# ESP32Shield.net
KiCad netlist of a schematic drawn in EAGLE
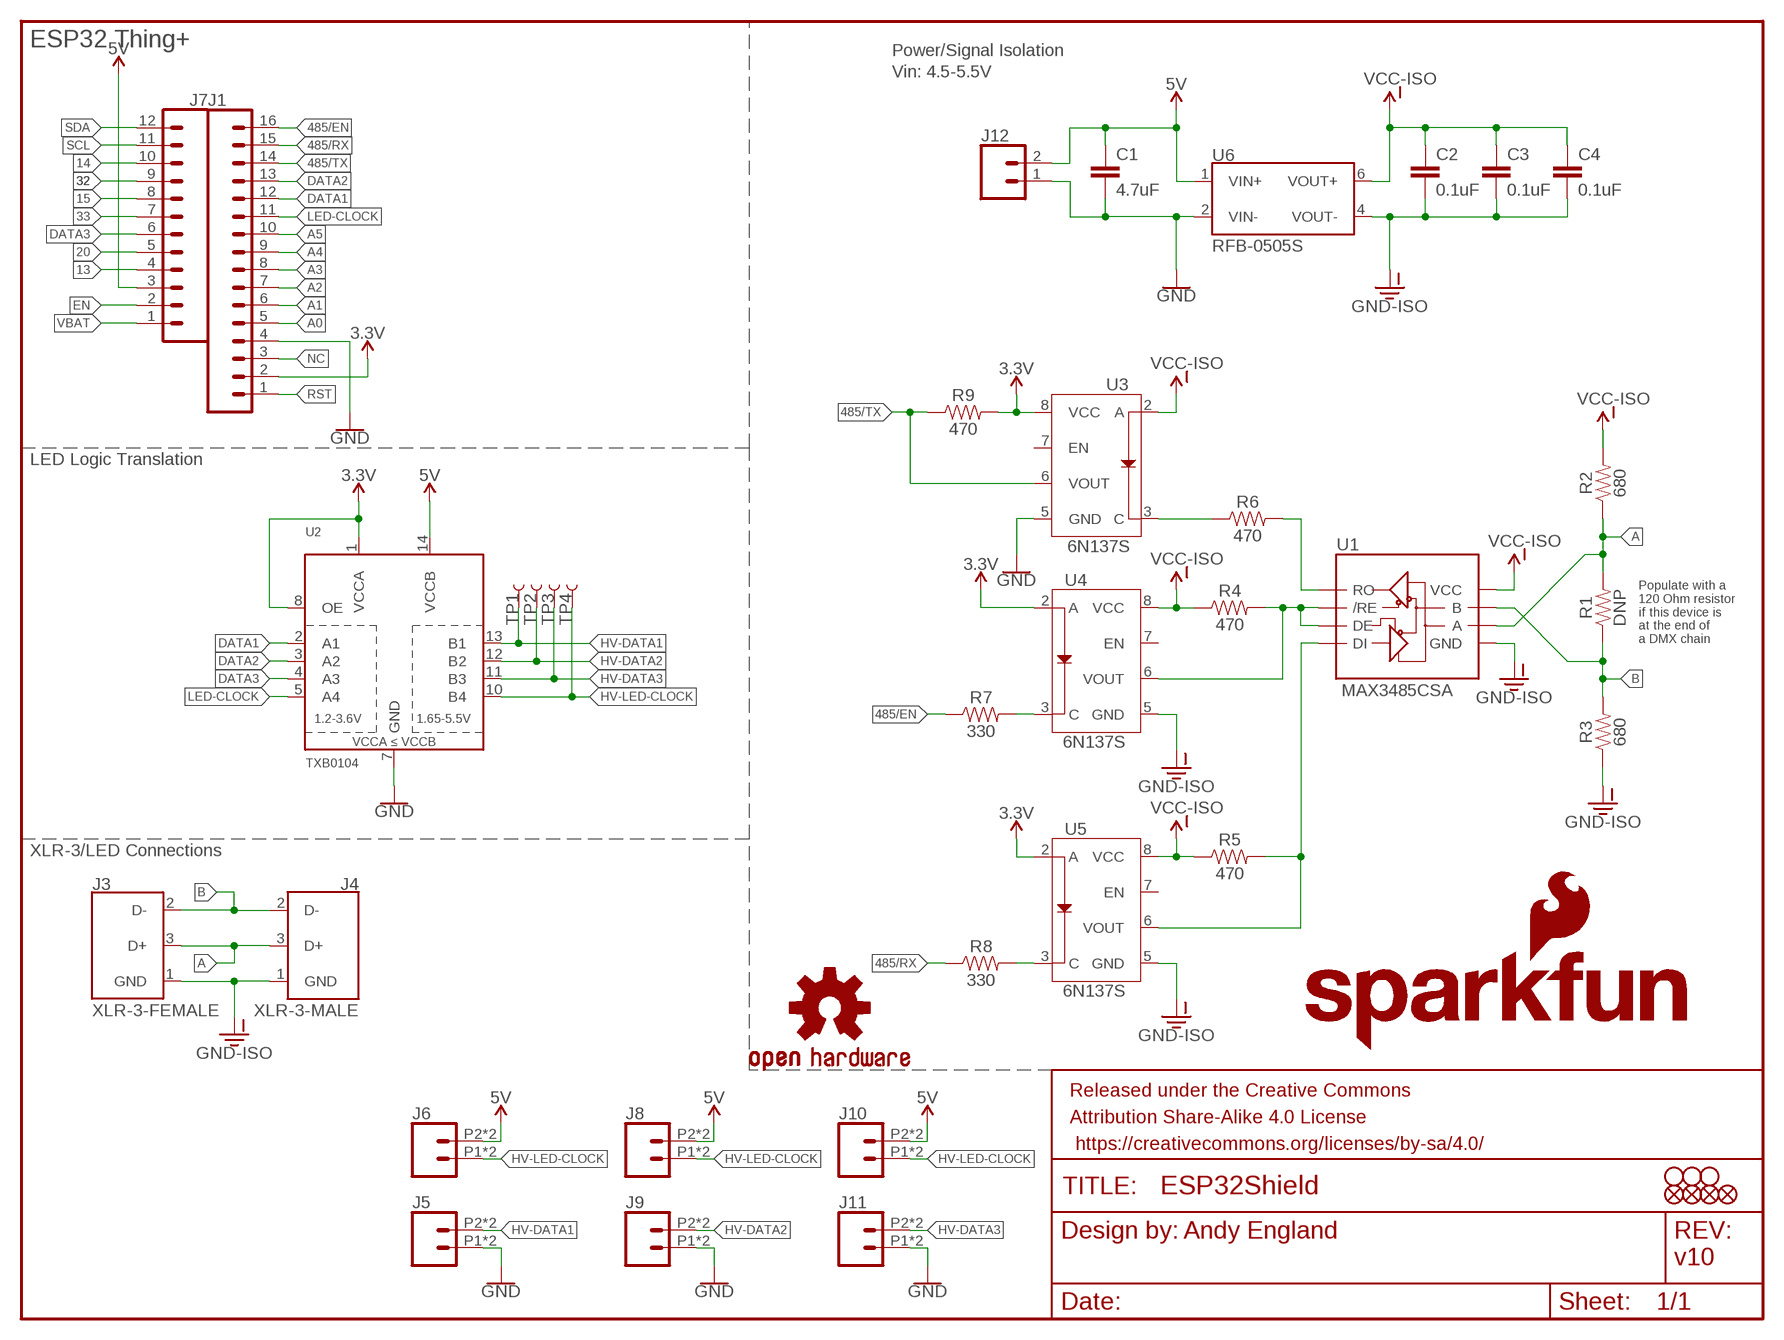
[diagram p0: schematic, sheet 1]

(export (version "E")
  (design (tool "Eeschema 10.0.6"))
  (components
    (comp (ref "C1")
      (value "4.7uF")
      (footprint "eagle-import:0603")
      (libsource (lib "eagle-import") (part "4.7UF-0603-6.3V-(10%)"))
    )
    (comp (ref "C2")
      (value "0.1uF")
      (footprint "eagle-import:0603")
      (libsource (lib "eagle-import") (part "0.1UF-0603-25V-(+80/-20%)"))
    )
    (comp (ref "C3")
      (value "0.1uF")
      (footprint "eagle-import:0603")
      (libsource (lib "eagle-import") (part "0.1UF-0603-25V-(+80/-20%)"))
    )
    (comp (ref "C4")
      (value "0.1uF")
      (footprint "eagle-import:0603")
      (libsource (lib "eagle-import") (part "0.1UF-0603-25V-(+80/-20%)"))
    )
    (comp (ref "FD1")
      (value "FIDUCIALUFIDUCIAL")
      (footprint "eagle-import:FIDUCIAL-MICRO")
      (libsource (lib "eagle-import") (part "FIDUCIALUFIDUCIAL"))
    )
    (comp (ref "FD2")
      (value "FIDUCIALUFIDUCIAL")
      (footprint "eagle-import:FIDUCIAL-MICRO")
      (libsource (lib "eagle-import") (part "FIDUCIALUFIDUCIAL"))
    )
    (comp (ref "FD3")
      (value "FIDUCIALUFIDUCIAL")
      (footprint "eagle-import:FIDUCIAL-MICRO")
      (libsource (lib "eagle-import") (part "FIDUCIALUFIDUCIAL"))
    )
    (comp (ref "FD4")
      (value "FIDUCIALUFIDUCIAL")
      (footprint "eagle-import:FIDUCIAL-MICRO")
      (libsource (lib "eagle-import") (part "FIDUCIALUFIDUCIAL"))
    )
    (comp (ref "FRAME1")
      (value "FRAME-LETTER")
      (footprint "eagle-import:CREATIVE_COMMONS")
      (libsource (lib "eagle-import") (part "FRAME-LETTER"))
    )
    (comp (ref "H1")
      (value "STAND-OFFTIGHT")
      (footprint "eagle-import:STAND-OFF-TIGHT")
      (libsource (lib "eagle-import") (part "STAND-OFFTIGHT"))
    )
    (comp (ref "H2")
      (value "STAND-OFFTIGHT")
      (footprint "eagle-import:STAND-OFF-TIGHT")
      (libsource (lib "eagle-import") (part "STAND-OFFTIGHT"))
    )
    (comp (ref "H3")
      (value "STAND-OFFTIGHT")
      (footprint "eagle-import:STAND-OFF-TIGHT")
      (libsource (lib "eagle-import") (part "STAND-OFFTIGHT"))
    )
    (comp (ref "J1")
      (value "CONN_16LOCK_NO_SILK")
      (footprint "eagle-import:1X16_LOCK_NO_SILK")
      (libsource (lib "eagle-import") (part "CONN_16LOCK_NO_SILK"))
    )
    (comp (ref "J3")
      (value "XLR-3-FEMALE")
      (footprint "eagle-import:XLR-3_FEMALE")
      (libsource (lib "eagle-import") (part "XLR-3-FEMALE"))
    )
    (comp (ref "J4")
      (value "XLR-3-MALE")
      (footprint "eagle-import:XLR-3_MALE")
      (libsource (lib "eagle-import") (part "XLR-3-MALE"))
    )
    (comp (ref "J5")
      (value "CONN_02SMALL_POKEHOME")
      (footprint "eagle-import:1X02_POKEHOME")
      (libsource (lib "eagle-import") (part "CONN_02SMALL_POKEHOME"))
    )
    (comp (ref "J6")
      (value "CONN_02SMALL_POKEHOME")
      (footprint "eagle-import:1X02_POKEHOME")
      (libsource (lib "eagle-import") (part "CONN_02SMALL_POKEHOME"))
    )
    (comp (ref "J7")
      (value "CONN_12LOCK_NO_SILK")
      (footprint "eagle-import:1X12_LOCK_NO_SILK")
      (libsource (lib "eagle-import") (part "CONN_12LOCK_NO_SILK"))
    )
    (comp (ref "J8")
      (value "CONN_02SMALL_POKEHOME")
      (footprint "eagle-import:1X02_POKEHOME")
      (libsource (lib "eagle-import") (part "CONN_02SMALL_POKEHOME"))
    )
    (comp (ref "J9")
      (value "CONN_02SMALL_POKEHOME")
      (footprint "eagle-import:1X02_POKEHOME")
      (libsource (lib "eagle-import") (part "CONN_02SMALL_POKEHOME"))
    )
    (comp (ref "J10")
      (value "CONN_02SMALL_POKEHOME")
      (footprint "eagle-import:1X02_POKEHOME")
      (libsource (lib "eagle-import") (part "CONN_02SMALL_POKEHOME"))
    )
    (comp (ref "J11")
      (value "CONN_02SMALL_POKEHOME")
      (footprint "eagle-import:1X02_POKEHOME")
      (libsource (lib "eagle-import") (part "CONN_02SMALL_POKEHOME"))
    )
    (comp (ref "J12")
      (value "CONN_023.5MM")
      (footprint "eagle-import:SCREWTERMINAL-3.5MM-2")
      (libsource (lib "eagle-import") (part "CONN_023.5MM"))
    )
    (comp (ref "LOGO1")
      (value "SFE_LOGO_NAME_FLAME.2_INCH")
      (footprint "eagle-import:SFE_LOGO_NAME_FLAME_.2")
      (libsource (lib "eagle-import") (part "SFE_LOGO_NAME_FLAME.2_INCH"))
    )
    (comp (ref "LOGO2")
      (value "SFE_LOGO_NAME_FLAME.2_INCH")
      (footprint "eagle-import:SFE_LOGO_NAME_FLAME_.2")
      (libsource (lib "eagle-import") (part "SFE_LOGO_NAME_FLAME.2_INCH"))
    )
    (comp (ref "LOGO3")
      (value "OSHW-LOGOS")
      (footprint "eagle-import:OSHW-LOGO-S")
      (libsource (lib "eagle-import") (part "OSHW-LOGOS"))
    )
    (comp (ref "R1")
      (value "DNP")
      (footprint "eagle-import:AXIAL-0.3EZ")
      (libsource (lib "eagle-import") (part "100OHM-HORIZ_KIT-1/4W-1%"))
    )
    (comp (ref "R2")
      (value "680")
      (footprint "eagle-import:0603")
      (libsource (lib "eagle-import") (part "680OHM-0603-1/10W-5%"))
    )
    (comp (ref "R3")
      (value "680")
      (footprint "eagle-import:0603")
      (libsource (lib "eagle-import") (part "680OHM-0603-1/10W-5%"))
    )
    (comp (ref "R4")
      (value "470")
      (footprint "eagle-import:0603")
      (libsource (lib "eagle-import") (part "470OHM-0603-1/10W-1%"))
    )
    (comp (ref "R5")
      (value "470")
      (footprint "eagle-import:0603")
      (libsource (lib "eagle-import") (part "470OHM-0603-1/10W-1%"))
    )
    (comp (ref "R6")
      (value "470")
      (footprint "eagle-import:0603")
      (libsource (lib "eagle-import") (part "470OHM-0603-1/10W-1%"))
    )
    (comp (ref "R7")
      (value "330")
      (footprint "eagle-import:0603")
      (libsource (lib "eagle-import") (part "330OHM-0603-1/10W-1%"))
    )
    (comp (ref "R8")
      (value "330")
      (footprint "eagle-import:0603")
      (libsource (lib "eagle-import") (part "330OHM-0603-1/10W-1%"))
    )
    (comp (ref "R9")
      (value "470")
      (footprint "eagle-import:0603")
      (libsource (lib "eagle-import") (part "470OHM-0603-1/10W-1%"))
    )
    (comp (ref "TP1")
      (value "TEST-POINT3")
      (footprint "eagle-import:PAD.03X.03")
      (libsource (lib "eagle-import") (part "TEST-POINT3"))
    )
    (comp (ref "TP2")
      (value "TEST-POINT3")
      (footprint "eagle-import:PAD.03X.03")
      (libsource (lib "eagle-import") (part "TEST-POINT3"))
    )
    (comp (ref "TP3")
      (value "TEST-POINT3")
      (footprint "eagle-import:PAD.03X.03")
      (libsource (lib "eagle-import") (part "TEST-POINT3"))
    )
    (comp (ref "TP4")
      (value "TEST-POINT3")
      (footprint "eagle-import:PAD.03X.03")
      (libsource (lib "eagle-import") (part "TEST-POINT3"))
    )
    (comp (ref "U1")
      (value "MAX3485CSA")
      (footprint "eagle-import:SO08")
      (libsource (lib "eagle-import") (part "RS485SOIC"))
    )
    (comp (ref "U2")
      (value "TXB0104")
      (footprint "eagle-import:TSSOP14")
      (libsource (lib "eagle-import") (part "TXB0104PWR"))
    )
    (comp (ref "U3")
      (value "6N137S")
      (footprint "eagle-import:8-SMD")
      (libsource (lib "eagle-import") (part "6N137S"))
    )
    (comp (ref "U4")
      (value "6N137S")
      (footprint "eagle-import:8-SMD")
      (libsource (lib "eagle-import") (part "6N137S"))
    )
    (comp (ref "U5")
      (value "6N137S")
      (footprint "eagle-import:8-SMD")
      (libsource (lib "eagle-import") (part "6N137S"))
    )
    (comp (ref "U6")
      (value "RFB-0505S")
      (footprint "eagle-import:RFB-0505S")
      (libsource (lib "eagle-import") (part "RFB-0505S"))
    )
  )
  (nets
    (net (code "1") (name "3.3V") (class "Default")
      (node (ref "J1") (pin "2") (pinfunction "2_2") (pintype "passive"))
      (node (ref "R9") (pin "2") (pinfunction "2_2") (pintype "passive"))
      (node (ref "U2") (pin "1") (pinfunction "VCCA_1") (pintype "bidirectional"))
      (node (ref "U2") (pin "8") (pinfunction "OE_8") (pintype "bidirectional"))
      (node (ref "U3") (pin "8") (pinfunction "VCC_8") (pintype "bidirectional"))
      (node (ref "U4") (pin "2") (pinfunction "A_2") (pintype "bidirectional"))
      (node (ref "U5") (pin "2") (pinfunction "A_2") (pintype "bidirectional"))
    )
    (net (code "2") (name "5V") (class "Default")
      (node (ref "C1") (pin "1") (pinfunction "1_1") (pintype "passive"))
      (node (ref "J10") (pin "P2") (pinfunction "2_P2") (pintype "passive"))
      (node (ref "J10") (pin "P4") (pinfunction "2_P4") (pintype "passive"))
      (node (ref "J12") (pin "2") (pinfunction "2_2") (pintype "passive"))
      (node (ref "J6") (pin "P2") (pinfunction "2_P2") (pintype "passive"))
      (node (ref "J6") (pin "P4") (pinfunction "2_P4") (pintype "passive"))
      (node (ref "J7") (pin "3") (pinfunction "3_3") (pintype "passive"))
      (node (ref "J8") (pin "P2") (pinfunction "2_P2") (pintype "passive"))
      (node (ref "J8") (pin "P4") (pinfunction "2_P4") (pintype "passive"))
      (node (ref "U2") (pin "14") (pinfunction "VCCB_14") (pintype "bidirectional"))
      (node (ref "U6") (pin "1") (pinfunction "VIN+_1") (pintype "bidirectional"))
    )
    (net (code "3") (name "13") (class "Default")
      (node (ref "J7") (pin "4") (pinfunction "4_4") (pintype "passive"))
    )
    (net (code "4") (name "14") (class "Default")
      (node (ref "J7") (pin "10") (pinfunction "10_10") (pintype "passive"))
    )
    (net (code "5") (name "15") (class "Default")
      (node (ref "J7") (pin "8") (pinfunction "8_8") (pintype "passive"))
    )
    (net (code "6") (name "20") (class "Default")
      (node (ref "J7") (pin "5") (pinfunction "5_5") (pintype "passive"))
    )
    (net (code "7") (name "32") (class "Default")
      (node (ref "J7") (pin "9") (pinfunction "9_9") (pintype "passive"))
    )
    (net (code "8") (name "33") (class "Default")
      (node (ref "J7") (pin "7") (pinfunction "7_7") (pintype "passive"))
    )
    (net (code "9") (name "485{slash}EN") (class "Default")
      (node (ref "J1") (pin "16") (pinfunction "16_16") (pintype "passive"))
      (node (ref "R7") (pin "1") (pinfunction "1_1") (pintype "passive"))
    )
    (net (code "10") (name "485{slash}RX") (class "Default")
      (node (ref "J1") (pin "15") (pinfunction "15_15") (pintype "passive"))
      (node (ref "R8") (pin "1") (pinfunction "1_1") (pintype "passive"))
    )
    (net (code "11") (name "485{slash}TX") (class "Default")
      (node (ref "J1") (pin "14") (pinfunction "14_14") (pintype "passive"))
      (node (ref "R9") (pin "1") (pinfunction "1_1") (pintype "passive"))
      (node (ref "U3") (pin "6") (pinfunction "VOUT_6") (pintype "bidirectional"))
    )
    (net (code "12") (name "A") (class "Default")
      (node (ref "J3") (pin "3") (pinfunction "D+_3") (pintype "bidirectional"))
      (node (ref "J4") (pin "3") (pinfunction "D+_3") (pintype "bidirectional"))
      (node (ref "R1") (pin "P$2") (pinfunction "2_P$2") (pintype "passive"))
      (node (ref "R2") (pin "1") (pinfunction "1_1") (pintype "passive"))
      (node (ref "U1") (pin "6") (pinfunction "A_6") (pintype "bidirectional"))
    )
    (net (code "13") (name "A0") (class "Default")
      (node (ref "J1") (pin "5") (pinfunction "5_5") (pintype "passive"))
    )
    (net (code "14") (name "A1") (class "Default")
      (node (ref "J1") (pin "6") (pinfunction "6_6") (pintype "passive"))
    )
    (net (code "15") (name "A2") (class "Default")
      (node (ref "J1") (pin "7") (pinfunction "7_7") (pintype "passive"))
    )
    (net (code "16") (name "A3") (class "Default")
      (node (ref "J1") (pin "8") (pinfunction "8_8") (pintype "passive"))
    )
    (net (code "17") (name "A4") (class "Default")
      (node (ref "J1") (pin "9") (pinfunction "9_9") (pintype "passive"))
    )
    (net (code "18") (name "A5") (class "Default")
      (node (ref "J1") (pin "10") (pinfunction "10_10") (pintype "passive"))
    )
    (net (code "19") (name "B") (class "Default")
      (node (ref "J3") (pin "2") (pinfunction "D-_2") (pintype "bidirectional"))
      (node (ref "J4") (pin "2") (pinfunction "D-_2") (pintype "bidirectional"))
      (node (ref "R1") (pin "P$1") (pinfunction "1_P$1") (pintype "passive"))
      (node (ref "R3") (pin "2") (pinfunction "2_2") (pintype "passive"))
      (node (ref "U1") (pin "7") (pinfunction "B_7") (pintype "bidirectional"))
    )
    (net (code "20") (name "DATA1") (class "Default")
      (node (ref "J1") (pin "12") (pinfunction "12_12") (pintype "passive"))
      (node (ref "U2") (pin "2") (pinfunction "A1_2") (pintype "bidirectional"))
    )
    (net (code "21") (name "DATA2") (class "Default")
      (node (ref "J1") (pin "13") (pinfunction "13_13") (pintype "passive"))
      (node (ref "U2") (pin "3") (pinfunction "A2_3") (pintype "bidirectional"))
    )
    (net (code "22") (name "DATA3") (class "Default")
      (node (ref "J7") (pin "6") (pinfunction "6_6") (pintype "passive"))
      (node (ref "U2") (pin "4") (pinfunction "A3_4") (pintype "bidirectional"))
    )
    (net (code "23") (name "EN") (class "Default")
      (node (ref "J7") (pin "2") (pinfunction "2_2") (pintype "passive"))
    )
    (net (code "24") (name "GND") (class "Default")
      (node (ref "C1") (pin "2") (pinfunction "2_2") (pintype "passive"))
      (node (ref "J1") (pin "4") (pinfunction "4_4") (pintype "passive"))
      (node (ref "J11") (pin "P1") (pinfunction "1_P1") (pintype "passive"))
      (node (ref "J11") (pin "P3") (pinfunction "1_P3") (pintype "passive"))
      (node (ref "J12") (pin "1") (pinfunction "1_1") (pintype "passive"))
      (node (ref "J5") (pin "P1") (pinfunction "1_P1") (pintype "passive"))
      (node (ref "J5") (pin "P3") (pinfunction "1_P3") (pintype "passive"))
      (node (ref "J9") (pin "P1") (pinfunction "1_P1") (pintype "passive"))
      (node (ref "J9") (pin "P3") (pinfunction "1_P3") (pintype "passive"))
      (node (ref "U2") (pin "7") (pinfunction "GND_7") (pintype "bidirectional"))
      (node (ref "U3") (pin "5") (pinfunction "GND_5") (pintype "bidirectional"))
      (node (ref "U6") (pin "2") (pinfunction "VIN-_2") (pintype "bidirectional"))
    )
    (net (code "25") (name "GND-ISO") (class "Default")
      (node (ref "C2") (pin "2") (pinfunction "2_2") (pintype "passive"))
      (node (ref "C3") (pin "2") (pinfunction "2_2") (pintype "passive"))
      (node (ref "C4") (pin "2") (pinfunction "2_2") (pintype "passive"))
      (node (ref "J3") (pin "1") (pinfunction "GND_1") (pintype "bidirectional"))
      (node (ref "J4") (pin "1") (pinfunction "GND_1") (pintype "bidirectional"))
      (node (ref "R3") (pin "1") (pinfunction "1_1") (pintype "passive"))
      (node (ref "U1") (pin "5") (pinfunction "GND_5") (pintype "bidirectional"))
      (node (ref "U4") (pin "5") (pinfunction "GND_5") (pintype "bidirectional"))
      (node (ref "U5") (pin "5") (pinfunction "GND_5") (pintype "bidirectional"))
      (node (ref "U6") (pin "4") (pinfunction "VOUT-_4") (pintype "bidirectional"))
    )
    (net (code "26") (name "HV-DATA1") (class "Default")
      (node (ref "J5") (pin "P2") (pinfunction "2_P2") (pintype "passive"))
      (node (ref "J5") (pin "P4") (pinfunction "2_P4") (pintype "passive"))
      (node (ref "TP1") (pin "P$1") (pinfunction "1_P$1") (pintype "bidirectional"))
      (node (ref "U2") (pin "13") (pinfunction "B1_13") (pintype "bidirectional"))
    )
    (net (code "27") (name "HV-DATA2") (class "Default")
      (node (ref "J9") (pin "P2") (pinfunction "2_P2") (pintype "passive"))
      (node (ref "J9") (pin "P4") (pinfunction "2_P4") (pintype "passive"))
      (node (ref "TP2") (pin "P$1") (pinfunction "1_P$1") (pintype "bidirectional"))
      (node (ref "U2") (pin "12") (pinfunction "B2_12") (pintype "bidirectional"))
    )
    (net (code "28") (name "HV-DATA3") (class "Default")
      (node (ref "J11") (pin "P2") (pinfunction "2_P2") (pintype "passive"))
      (node (ref "J11") (pin "P4") (pinfunction "2_P4") (pintype "passive"))
      (node (ref "TP3") (pin "P$1") (pinfunction "1_P$1") (pintype "bidirectional"))
      (node (ref "U2") (pin "11") (pinfunction "B3_11") (pintype "bidirectional"))
    )
    (net (code "29") (name "HV-LED-CLOCK") (class "Default")
      (node (ref "J10") (pin "P1") (pinfunction "1_P1") (pintype "passive"))
      (node (ref "J10") (pin "P3") (pinfunction "1_P3") (pintype "passive"))
      (node (ref "J6") (pin "P1") (pinfunction "1_P1") (pintype "passive"))
      (node (ref "J6") (pin "P3") (pinfunction "1_P3") (pintype "passive"))
      (node (ref "J8") (pin "P1") (pinfunction "1_P1") (pintype "passive"))
      (node (ref "J8") (pin "P3") (pinfunction "1_P3") (pintype "passive"))
      (node (ref "TP4") (pin "P$1") (pinfunction "1_P$1") (pintype "bidirectional"))
      (node (ref "U2") (pin "10") (pinfunction "B4_10") (pintype "bidirectional"))
    )
    (net (code "30") (name "LED-CLOCK") (class "Default")
      (node (ref "J1") (pin "11") (pinfunction "11_11") (pintype "passive"))
      (node (ref "U2") (pin "5") (pinfunction "A4_5") (pintype "bidirectional"))
    )
    (net (code "31") (name "NC") (class "Default")
      (node (ref "J1") (pin "3") (pinfunction "3_3") (pintype "passive"))
    )
    (net (code "32") (name "Net-(U1-DE)") (class "Default")
      (node (ref "R4") (pin "2") (pinfunction "2_2") (pintype "passive"))
      (node (ref "U1") (pin "2") (pinfunction "/RE_2") (pintype "bidirectional"))
      (node (ref "U1") (pin "3") (pinfunction "DE_3") (pintype "bidirectional"))
      (node (ref "U4") (pin "6") (pinfunction "VOUT_6") (pintype "bidirectional"))
    )
    (net (code "33") (name "Net-(U1-DI)") (class "Default")
      (node (ref "R5") (pin "2") (pinfunction "2_2") (pintype "passive"))
      (node (ref "U1") (pin "4") (pinfunction "DI_4") (pintype "bidirectional"))
      (node (ref "U5") (pin "6") (pinfunction "VOUT_6") (pintype "bidirectional"))
    )
    (net (code "34") (name "Net-(U1-RO)") (class "Default")
      (node (ref "R6") (pin "2") (pinfunction "2_2") (pintype "passive"))
      (node (ref "U1") (pin "1") (pinfunction "RO_1") (pintype "bidirectional"))
    )
    (net (code "35") (name "Net-(U3-C)") (class "Default")
      (node (ref "R6") (pin "1") (pinfunction "1_1") (pintype "passive"))
      (node (ref "U3") (pin "3") (pinfunction "C_3") (pintype "bidirectional"))
    )
    (net (code "36") (name "Net-(U4-C)") (class "Default")
      (node (ref "R7") (pin "2") (pinfunction "2_2") (pintype "passive"))
      (node (ref "U4") (pin "3") (pinfunction "C_3") (pintype "bidirectional"))
    )
    (net (code "37") (name "Net-(U5-C)") (class "Default")
      (node (ref "R8") (pin "2") (pinfunction "2_2") (pintype "passive"))
      (node (ref "U5") (pin "3") (pinfunction "C_3") (pintype "bidirectional"))
    )
    (net (code "38") (name "RST") (class "Default")
      (node (ref "J1") (pin "1") (pinfunction "1_1") (pintype "passive"))
    )
    (net (code "39") (name "SCL") (class "Default")
      (node (ref "J7") (pin "11") (pinfunction "11_11") (pintype "passive"))
    )
    (net (code "40") (name "SDA") (class "Default")
      (node (ref "J7") (pin "12") (pinfunction "12_12") (pintype "passive"))
    )
    (net (code "41") (name "VBAT") (class "Default")
      (node (ref "J7") (pin "1") (pinfunction "1_1") (pintype "passive"))
    )
    (net (code "42") (name "VCC-ISO") (class "Default")
      (node (ref "C2") (pin "1") (pinfunction "1_1") (pintype "passive"))
      (node (ref "C3") (pin "1") (pinfunction "1_1") (pintype "passive"))
      (node (ref "C4") (pin "1") (pinfunction "1_1") (pintype "passive"))
      (node (ref "R2") (pin "2") (pinfunction "2_2") (pintype "passive"))
      (node (ref "R4") (pin "1") (pinfunction "1_1") (pintype "passive"))
      (node (ref "R5") (pin "1") (pinfunction "1_1") (pintype "passive"))
      (node (ref "U1") (pin "8") (pinfunction "VCC_8") (pintype "bidirectional"))
      (node (ref "U3") (pin "2") (pinfunction "A_2") (pintype "bidirectional"))
      (node (ref "U4") (pin "8") (pinfunction "VCC_8") (pintype "bidirectional"))
      (node (ref "U5") (pin "8") (pinfunction "VCC_8") (pintype "bidirectional"))
      (node (ref "U6") (pin "6") (pinfunction "VOUT+_6") (pintype "bidirectional"))
    )
    (net (code "43") (name "unconnected-(U3-EN-Pad7)") (class "Default")
      (node (ref "U3") (pin "7") (pinfunction "EN_7") (pintype "bidirectional"))
    )
    (net (code "44") (name "unconnected-(U4-EN-Pad7)") (class "Default")
      (node (ref "U4") (pin "7") (pinfunction "EN_7") (pintype "bidirectional"))
    )
    (net (code "45") (name "unconnected-(U5-EN-Pad7)") (class "Default")
      (node (ref "U5") (pin "7") (pinfunction "EN_7") (pintype "bidirectional"))
    )
  )
)
